# IsolatedPowerControl.net
KiCad netlist of a schematic drawn in EAGLE
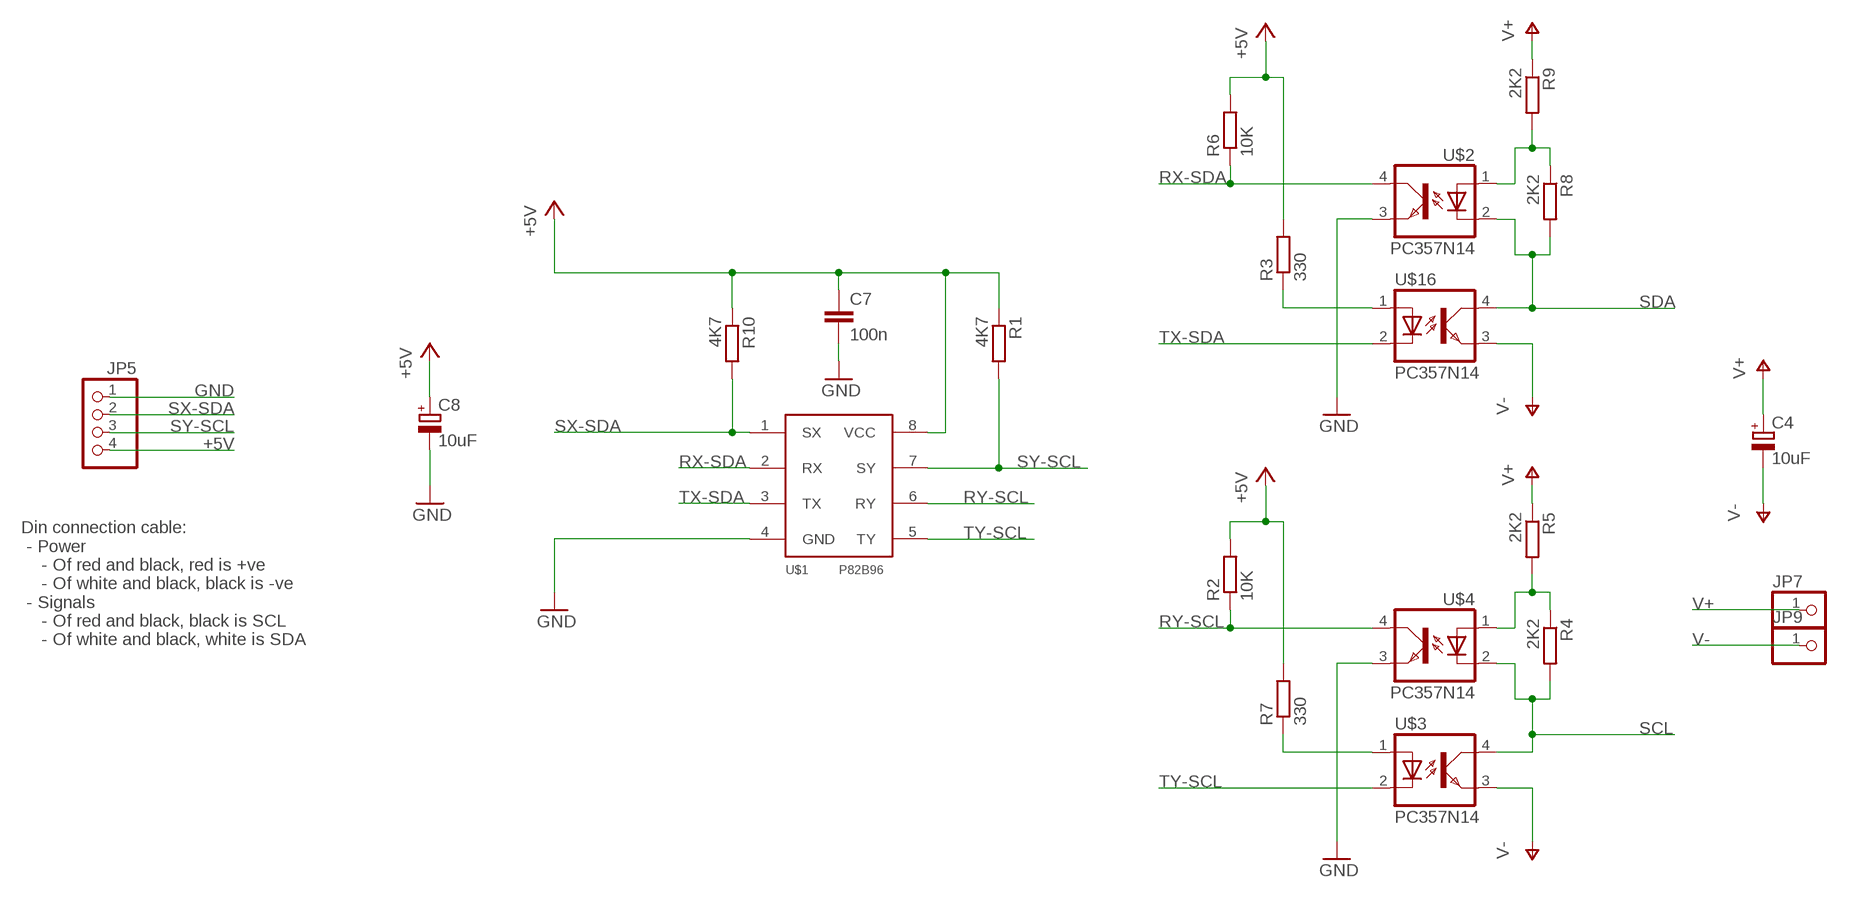
[diagram p0: schematic, sheet 1, part 1 of 2]
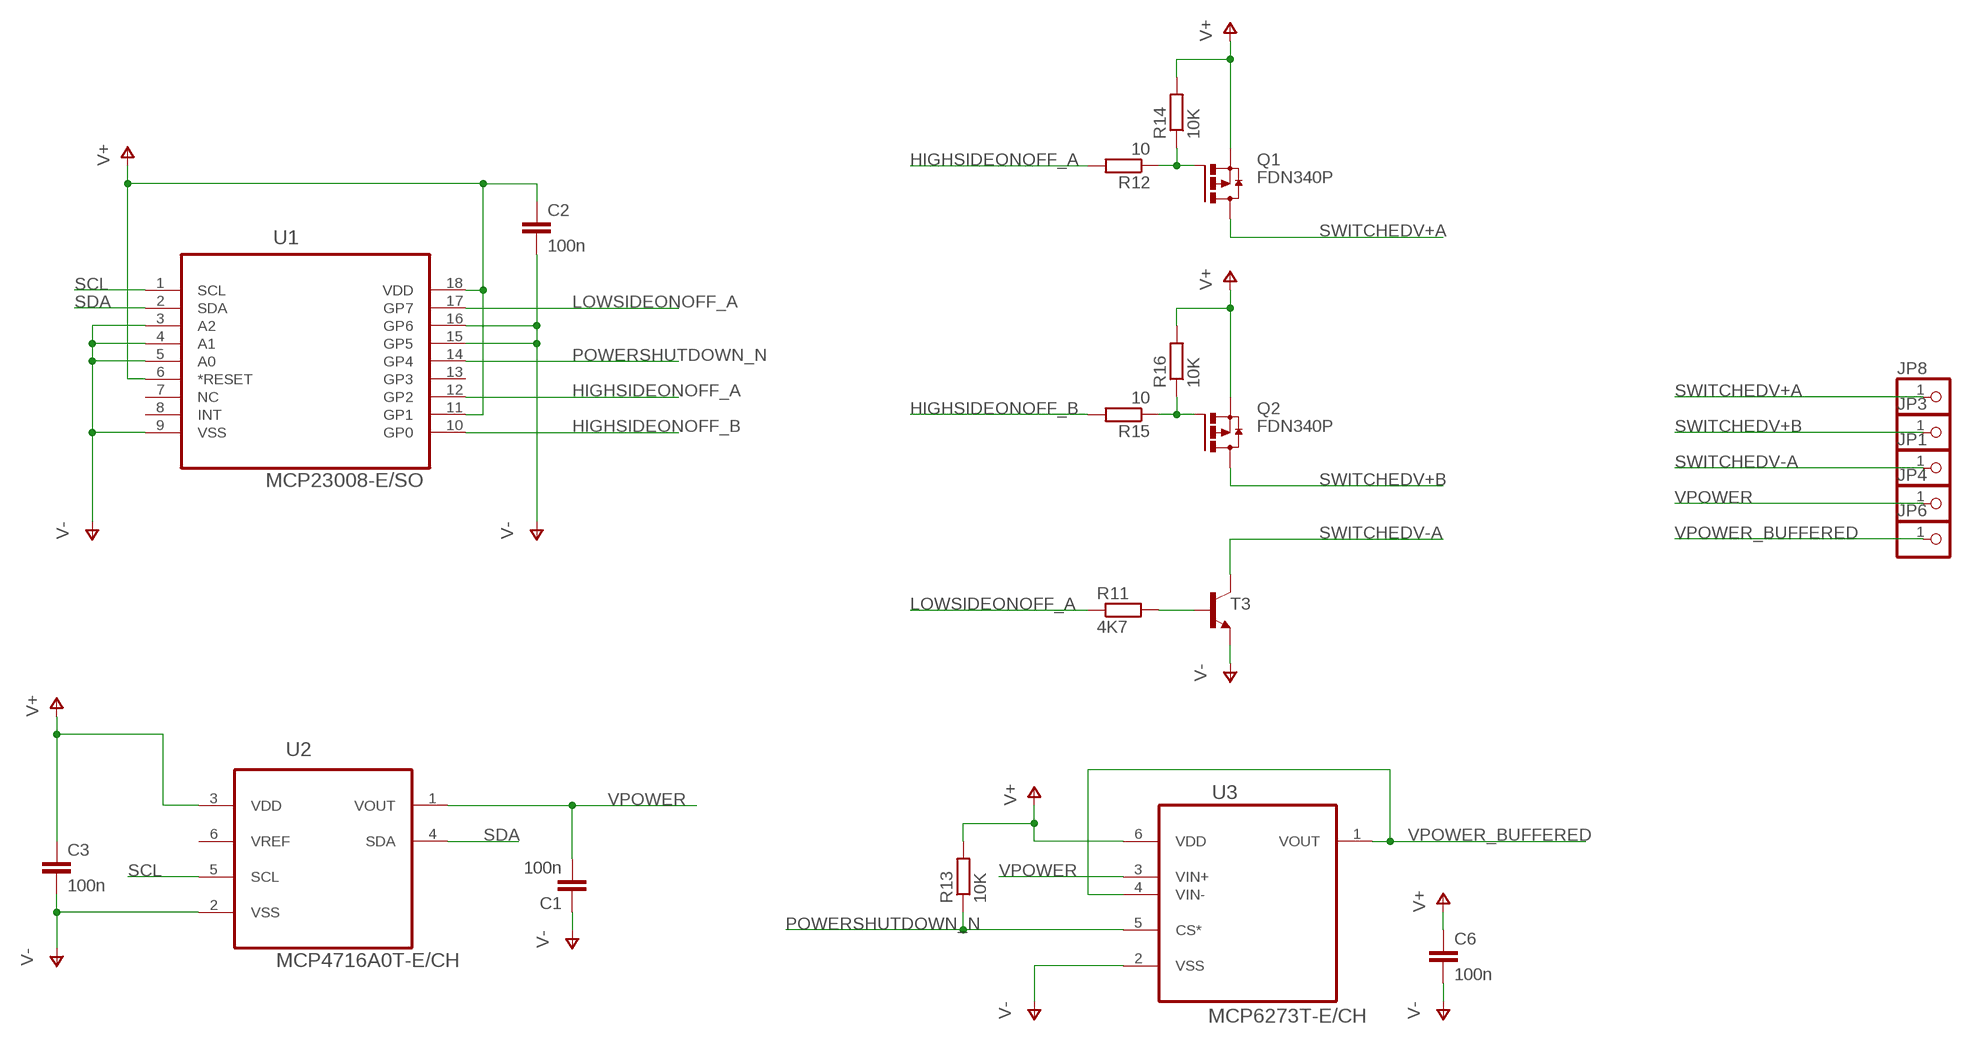
[diagram p1: schematic, sheet 1, part 2 of 2]

(export (version "E")
  (design (tool "Eeschema 10.0.6"))
  (components
    (comp (ref "C1")
      (value "100n")
      (footprint "eagle-import:C1206K")
      (libsource (lib "eagle-import") (part "C-EUC1206K"))
    )
    (comp (ref "C2")
      (value "100n")
      (footprint "eagle-import:C1206K")
      (libsource (lib "eagle-import") (part "C-EUC1206K"))
    )
    (comp (ref "C3")
      (value "100n")
      (footprint "eagle-import:C1206K")
      (libsource (lib "eagle-import") (part "C-EUC1206K"))
    )
    (comp (ref "C4")
      (value "10uF")
      (footprint "eagle-import:E2-5")
      (libsource (lib "eagle-import") (part "CPOL-EUE2-5"))
    )
    (comp (ref "C6")
      (value "100n")
      (footprint "eagle-import:C1206K")
      (libsource (lib "eagle-import") (part "C-EUC1206K"))
    )
    (comp (ref "C7")
      (value "100n")
      (footprint "eagle-import:C1206K")
      (libsource (lib "eagle-import") (part "C-EUC1206K"))
    )
    (comp (ref "C8")
      (value "10uF")
      (footprint "eagle-import:E2-5")
      (libsource (lib "eagle-import") (part "CPOL-EUE2-5"))
    )
    (comp (ref "JP1")
      (value "PINHD-1X1LARGEPAD")
      (footprint "eagle-import:1X01-LARGEPAD")
      (libsource (lib "eagle-import") (part "PINHD-1X1LARGEPAD"))
    )
    (comp (ref "JP3")
      (value "PINHD-1X1LARGEPAD")
      (footprint "eagle-import:1X01-LARGEPAD")
      (libsource (lib "eagle-import") (part "PINHD-1X1LARGEPAD"))
    )
    (comp (ref "JP4")
      (value "PINHD-1X1LARGEPAD")
      (footprint "eagle-import:1X01-LARGEPAD")
      (libsource (lib "eagle-import") (part "PINHD-1X1LARGEPAD"))
    )
    (comp (ref "JP5")
      (value "PINHD-1X4")
      (footprint "eagle-import:1X04")
      (libsource (lib "eagle-import") (part "PINHD-1X4"))
    )
    (comp (ref "JP6")
      (value "PINHD-1X1LARGEPAD")
      (footprint "eagle-import:1X01-LARGEPAD")
      (libsource (lib "eagle-import") (part "PINHD-1X1LARGEPAD"))
    )
    (comp (ref "JP7")
      (value "PINHD-1X1LARGEPAD")
      (footprint "eagle-import:1X01-LARGEPAD")
      (libsource (lib "eagle-import") (part "PINHD-1X1LARGEPAD"))
    )
    (comp (ref "JP8")
      (value "PINHD-1X1LARGEPAD")
      (footprint "eagle-import:1X01-LARGEPAD")
      (libsource (lib "eagle-import") (part "PINHD-1X1LARGEPAD"))
    )
    (comp (ref "JP9")
      (value "PINHD-1X1LARGEPAD")
      (footprint "eagle-import:1X01-LARGEPAD")
      (libsource (lib "eagle-import") (part "PINHD-1X1LARGEPAD"))
    )
    (comp (ref "Q1")
      (value "FDN340P")
      (footprint "eagle-import:SUPER-SOT3")
      (libsource (lib "eagle-import") (part "FDN360P"))
    )
    (comp (ref "Q2")
      (value "FDN340P")
      (footprint "eagle-import:SUPER-SOT3")
      (libsource (lib "eagle-import") (part "FDN360P"))
    )
    (comp (ref "R1")
      (value "4K7")
      (footprint "eagle-import:R0402")
      (libsource (lib "eagle-import") (part "R-EU_R0402"))
    )
    (comp (ref "R2")
      (value "10K")
      (footprint "eagle-import:R0805")
      (libsource (lib "eagle-import") (part "R-EU_R0805"))
    )
    (comp (ref "R3")
      (value "330")
      (footprint "eagle-import:R0402")
      (libsource (lib "eagle-import") (part "R-EU_R0402"))
    )
    (comp (ref "R4")
      (value "2K2")
      (footprint "eagle-import:R0402")
      (libsource (lib "eagle-import") (part "R-EU_R0402"))
    )
    (comp (ref "R5")
      (value "2K2")
      (footprint "eagle-import:R0402")
      (libsource (lib "eagle-import") (part "R-EU_R0402"))
    )
    (comp (ref "R6")
      (value "10K")
      (footprint "eagle-import:R0805")
      (libsource (lib "eagle-import") (part "R-EU_R0805"))
    )
    (comp (ref "R7")
      (value "330")
      (footprint "eagle-import:R0402")
      (libsource (lib "eagle-import") (part "R-EU_R0402"))
    )
    (comp (ref "R8")
      (value "2K2")
      (footprint "eagle-import:R0402")
      (libsource (lib "eagle-import") (part "R-EU_R0402"))
    )
    (comp (ref "R9")
      (value "2K2")
      (footprint "eagle-import:R0402")
      (libsource (lib "eagle-import") (part "R-EU_R0402"))
    )
    (comp (ref "R10")
      (value "4K7")
      (footprint "eagle-import:R0402")
      (libsource (lib "eagle-import") (part "R-EU_R0402"))
    )
    (comp (ref "R11")
      (value "4K7")
      (footprint "eagle-import:R0402")
      (libsource (lib "eagle-import") (part "R-EU_R0402"))
    )
    (comp (ref "R12")
      (value "10")
      (footprint "eagle-import:R0603")
      (libsource (lib "eagle-import") (part "R-EU_R0603"))
    )
    (comp (ref "R13")
      (value "10K")
      (footprint "eagle-import:R0805")
      (libsource (lib "eagle-import") (part "R-EU_R0805"))
    )
    (comp (ref "R14")
      (value "10K")
      (footprint "eagle-import:R0805")
      (libsource (lib "eagle-import") (part "R-EU_R0805"))
    )
    (comp (ref "R15")
      (value "10")
      (footprint "eagle-import:R0603")
      (libsource (lib "eagle-import") (part "R-EU_R0603"))
    )
    (comp (ref "R16")
      (value "10K")
      (footprint "eagle-import:R0805")
      (libsource (lib "eagle-import") (part "R-EU_R0805"))
    )
    (comp (ref "T3")
      (value "MMBTA42LT1-NPN-SOT23-BEC")
      (footprint "eagle-import:SOT23-BEC")
      (libsource (lib "eagle-import") (part "-NPN-SOT23-BECMMBTA42LT1"))
    )
    (comp (ref "U$1")
      (value "P82B96")
      (footprint "eagle-import:SOIC8")
      (libsource (lib "eagle-import") (part "P82B96"))
    )
    (comp (ref "U$2")
      (value "PC357N14")
      (footprint "eagle-import:MINI-FLAT-4-DS")
      (libsource (lib "eagle-import") (part "PC357N14"))
    )
    (comp (ref "U$3")
      (value "PC357N14")
      (footprint "eagle-import:MINI-FLAT-4-DS")
      (libsource (lib "eagle-import") (part "PC357N14"))
    )
    (comp (ref "U$4")
      (value "PC357N14")
      (footprint "eagle-import:MINI-FLAT-4-DS")
      (libsource (lib "eagle-import") (part "PC357N14"))
    )
    (comp (ref "U$16")
      (value "PC357N14")
      (footprint "eagle-import:MINI-FLAT-4-DS")
      (libsource (lib "eagle-import") (part "PC357N14"))
    )
    (comp (ref "U1")
      (value "MCP23008-E/SO")
      (footprint "eagle-import:SOIC127P1030X265-18N")
      (libsource (lib "eagle-import") (part "MCP23008-E/SO"))
    )
    (comp (ref "U2")
      (value "MCP4716A0T-E/CH")
      (footprint "eagle-import:SOT95P270X145-6N")
      (libsource (lib "eagle-import") (part "MCP4716A0T-E/CH"))
    )
    (comp (ref "U3")
      (value "MCP6273T-E/CH")
      (footprint "eagle-import:SOT95P280X145-6N")
      (libsource (lib "eagle-import") (part "MCP6273T-E/CH"))
    )
  )
  (nets
    (net (code "1") (name "+5V") (class "Default")
      (node (ref "C7") (pin "1") (pinfunction "1_1") (pintype "passive"))
      (node (ref "C8") (pin "+") (pinfunction "+_+") (pintype "passive"))
      (node (ref "JP5") (pin "4") (pinfunction "4_4") (pintype "passive"))
      (node (ref "R1") (pin "1") (pinfunction "1_1") (pintype "passive"))
      (node (ref "R10") (pin "1") (pinfunction "1_1") (pintype "passive"))
      (node (ref "R2") (pin "2") (pinfunction "2_2") (pintype "passive"))
      (node (ref "R3") (pin "2") (pinfunction "2_2") (pintype "passive"))
      (node (ref "R6") (pin "2") (pinfunction "2_2") (pintype "passive"))
      (node (ref "R7") (pin "2") (pinfunction "2_2") (pintype "passive"))
      (node (ref "U$1") (pin "8") (pinfunction "VCC_8") (pintype "bidirectional"))
    )
    (net (code "2") (name "/HIGHSIDEONOFF_A") (class "Default")
      (node (ref "R12") (pin "2") (pinfunction "2_2") (pintype "passive"))
      (node (ref "U1") (pin "12") (pinfunction "GP2_12") (pintype "passive"))
    )
    (net (code "3") (name "/HIGHSIDEONOFF_B") (class "Default")
      (node (ref "R15") (pin "2") (pinfunction "2_2") (pintype "passive"))
      (node (ref "U1") (pin "10") (pinfunction "GP0_10") (pintype "passive"))
    )
    (net (code "4") (name "/LOWSIDEONOFF_A") (class "Default")
      (node (ref "R11") (pin "1") (pinfunction "1_1") (pintype "passive"))
      (node (ref "U1") (pin "17") (pinfunction "GP7_17") (pintype "passive"))
    )
    (net (code "5") (name "/POWERSHUTDOWN_N") (class "Default")
      (node (ref "R13") (pin "1") (pinfunction "1_1") (pintype "passive"))
      (node (ref "U1") (pin "14") (pinfunction "GP4_14") (pintype "passive"))
      (node (ref "U3") (pin "5") (pinfunction "CS*_5") (pintype "passive"))
    )
    (net (code "6") (name "/RX-SDA") (class "Default")
      (node (ref "R6") (pin "1") (pinfunction "1_1") (pintype "passive"))
      (node (ref "U$1") (pin "2") (pinfunction "RX_2") (pintype "bidirectional"))
      (node (ref "U$2") (pin "4") (pinfunction "COL_4") (pintype "passive"))
    )
    (net (code "7") (name "/RY-SCL") (class "Default")
      (node (ref "R2") (pin "1") (pinfunction "1_1") (pintype "passive"))
      (node (ref "U$1") (pin "6") (pinfunction "RY_6") (pintype "bidirectional"))
      (node (ref "U$4") (pin "4") (pinfunction "COL_4") (pintype "passive"))
    )
    (net (code "8") (name "/SCL") (class "Default")
      (node (ref "R4") (pin "2") (pinfunction "2_2") (pintype "passive"))
      (node (ref "U$3") (pin "4") (pinfunction "COL_4") (pintype "passive"))
      (node (ref "U$4") (pin "2") (pinfunction "C_2") (pintype "passive"))
      (node (ref "U1") (pin "1") (pinfunction "SCL_1") (pintype "input"))
      (node (ref "U2") (pin "5") (pinfunction "SCL_5") (pintype "input"))
    )
    (net (code "9") (name "/SDA") (class "Default")
      (node (ref "R8") (pin "2") (pinfunction "2_2") (pintype "passive"))
      (node (ref "U$16") (pin "4") (pinfunction "COL_4") (pintype "passive"))
      (node (ref "U$2") (pin "2") (pinfunction "C_2") (pintype "passive"))
      (node (ref "U1") (pin "2") (pinfunction "SDA_2") (pintype "passive"))
      (node (ref "U2") (pin "4") (pinfunction "SDA_4") (pintype "bidirectional"))
    )
    (net (code "10") (name "/SWITCHEDV+A") (class "Default")
      (node (ref "JP8") (pin "1") (pinfunction "1_1") (pintype "passive"))
      (node (ref "Q1") (pin "3") (pinfunction "D_3") (pintype "passive"))
    )
    (net (code "11") (name "/SWITCHEDV+B") (class "Default")
      (node (ref "JP3") (pin "1") (pinfunction "1_1") (pintype "passive"))
      (node (ref "Q2") (pin "3") (pinfunction "D_3") (pintype "passive"))
    )
    (net (code "12") (name "/SWITCHEDV-A") (class "Default")
      (node (ref "JP1") (pin "1") (pinfunction "1_1") (pintype "passive"))
      (node (ref "T3") (pin "C") (pinfunction "C_C") (pintype "passive"))
    )
    (net (code "13") (name "/SX-SDA") (class "Default")
      (node (ref "JP5") (pin "2") (pinfunction "2_2") (pintype "passive"))
      (node (ref "R10") (pin "2") (pinfunction "2_2") (pintype "passive"))
      (node (ref "U$1") (pin "1") (pinfunction "SX_1") (pintype "bidirectional"))
    )
    (net (code "14") (name "/SY-SCL") (class "Default")
      (node (ref "JP5") (pin "3") (pinfunction "3_3") (pintype "passive"))
      (node (ref "R1") (pin "2") (pinfunction "2_2") (pintype "passive"))
      (node (ref "U$1") (pin "7") (pinfunction "SY_7") (pintype "bidirectional"))
    )
    (net (code "15") (name "/TX-SDA") (class "Default")
      (node (ref "U$1") (pin "3") (pinfunction "TX_3") (pintype "bidirectional"))
      (node (ref "U$16") (pin "2") (pinfunction "C_2") (pintype "passive"))
    )
    (net (code "16") (name "/TY-SCL") (class "Default")
      (node (ref "U$1") (pin "5") (pinfunction "TY_5") (pintype "bidirectional"))
      (node (ref "U$3") (pin "2") (pinfunction "C_2") (pintype "passive"))
    )
    (net (code "17") (name "/VPOWER") (class "Default")
      (node (ref "C1") (pin "2") (pinfunction "2_2") (pintype "passive"))
      (node (ref "JP4") (pin "1") (pinfunction "1_1") (pintype "passive"))
      (node (ref "U2") (pin "1") (pinfunction "VOUT_1") (pintype "output"))
      (node (ref "U3") (pin "3") (pinfunction "VIN+_3") (pintype "input"))
    )
    (net (code "18") (name "/VPOWER_BUFFERED") (class "Default")
      (node (ref "JP6") (pin "1") (pinfunction "1_1") (pintype "passive"))
      (node (ref "U3") (pin "1") (pinfunction "VOUT_1") (pintype "output"))
      (node (ref "U3") (pin "4") (pinfunction "VIN-_4") (pintype "input"))
    )
    (net (code "19") (name "GND") (class "Default")
      (node (ref "C7") (pin "2") (pinfunction "2_2") (pintype "passive"))
      (node (ref "C8") (pin "-") (pinfunction "-_-") (pintype "passive"))
      (node (ref "JP5") (pin "1") (pinfunction "1_1") (pintype "passive"))
      (node (ref "U$1") (pin "4") (pinfunction "GND_4") (pintype "bidirectional"))
      (node (ref "U$2") (pin "3") (pinfunction "EMIT_3") (pintype "passive"))
      (node (ref "U$4") (pin "3") (pinfunction "EMIT_3") (pintype "passive"))
    )
    (net (code "20") (name "Net-(Q1-G)") (class "Default")
      (node (ref "Q1") (pin "1") (pinfunction "G_1") (pintype "passive"))
      (node (ref "R12") (pin "1") (pinfunction "1_1") (pintype "passive"))
      (node (ref "R14") (pin "1") (pinfunction "1_1") (pintype "passive"))
    )
    (net (code "21") (name "Net-(Q2-G)") (class "Default")
      (node (ref "Q2") (pin "1") (pinfunction "G_1") (pintype "passive"))
      (node (ref "R15") (pin "1") (pinfunction "1_1") (pintype "passive"))
      (node (ref "R16") (pin "1") (pinfunction "1_1") (pintype "passive"))
    )
    (net (code "22") (name "Net-(R11-Pad2)") (class "Default")
      (node (ref "R11") (pin "2") (pinfunction "2_2") (pintype "passive"))
      (node (ref "T3") (pin "B") (pinfunction "B_B") (pintype "passive"))
    )
    (net (code "23") (name "Net-(U$2-A)") (class "Default")
      (node (ref "R8") (pin "1") (pinfunction "1_1") (pintype "passive"))
      (node (ref "R9") (pin "2") (pinfunction "2_2") (pintype "passive"))
      (node (ref "U$2") (pin "1") (pinfunction "A_1") (pintype "passive"))
    )
    (net (code "24") (name "Net-(U$3-A)") (class "Default")
      (node (ref "R7") (pin "1") (pinfunction "1_1") (pintype "passive"))
      (node (ref "U$3") (pin "1") (pinfunction "A_1") (pintype "passive"))
    )
    (net (code "25") (name "Net-(U$4-A)") (class "Default")
      (node (ref "R4") (pin "1") (pinfunction "1_1") (pintype "passive"))
      (node (ref "R5") (pin "2") (pinfunction "2_2") (pintype "passive"))
      (node (ref "U$4") (pin "1") (pinfunction "A_1") (pintype "passive"))
    )
    (net (code "26") (name "Net-(U$16-A)") (class "Default")
      (node (ref "R3") (pin "1") (pinfunction "1_1") (pintype "passive"))
      (node (ref "U$16") (pin "1") (pinfunction "A_1") (pintype "passive"))
    )
    (net (code "27") (name "V+") (class "Default")
      (node (ref "C2") (pin "1") (pinfunction "1_1") (pintype "passive"))
      (node (ref "C3") (pin "1") (pinfunction "1_1") (pintype "passive"))
      (node (ref "C4") (pin "+") (pinfunction "+_+") (pintype "passive"))
      (node (ref "C6") (pin "1") (pinfunction "1_1") (pintype "passive"))
      (node (ref "JP7") (pin "1") (pinfunction "1_1") (pintype "passive"))
      (node (ref "Q1") (pin "2") (pinfunction "S_2") (pintype "passive"))
      (node (ref "Q2") (pin "2") (pinfunction "S_2") (pintype "passive"))
      (node (ref "R13") (pin "2") (pinfunction "2_2") (pintype "passive"))
      (node (ref "R14") (pin "2") (pinfunction "2_2") (pintype "passive"))
      (node (ref "R16") (pin "2") (pinfunction "2_2") (pintype "passive"))
      (node (ref "R5") (pin "1") (pinfunction "1_1") (pintype "passive"))
      (node (ref "R9") (pin "1") (pinfunction "1_1") (pintype "passive"))
      (node (ref "U1") (pin "11") (pinfunction "GP1_11") (pintype "passive"))
      (node (ref "U1") (pin "18") (pinfunction "VDD_18") (pintype "power_in"))
      (node (ref "U1") (pin "6") (pinfunction "*RESET_6") (pintype "input"))
      (node (ref "U2") (pin "3") (pinfunction "VDD_3") (pintype "power_in"))
      (node (ref "U3") (pin "6") (pinfunction "VDD_6") (pintype "power_in"))
    )
    (net (code "28") (name "V-") (class "Default")
      (node (ref "C1") (pin "1") (pinfunction "1_1") (pintype "passive"))
      (node (ref "C2") (pin "2") (pinfunction "2_2") (pintype "passive"))
      (node (ref "C3") (pin "2") (pinfunction "2_2") (pintype "passive"))
      (node (ref "C4") (pin "-") (pinfunction "-_-") (pintype "passive"))
      (node (ref "C6") (pin "2") (pinfunction "2_2") (pintype "passive"))
      (node (ref "JP9") (pin "1") (pinfunction "1_1") (pintype "passive"))
      (node (ref "T3") (pin "E") (pinfunction "E_E") (pintype "passive"))
      (node (ref "U$16") (pin "3") (pinfunction "EMIT_3") (pintype "passive"))
      (node (ref "U$3") (pin "3") (pinfunction "EMIT_3") (pintype "passive"))
      (node (ref "U1") (pin "15") (pinfunction "GP5_15") (pintype "passive"))
      (node (ref "U1") (pin "16") (pinfunction "GP6_16") (pintype "passive"))
      (node (ref "U1") (pin "3") (pinfunction "A2_3") (pintype "passive"))
      (node (ref "U1") (pin "4") (pinfunction "A1_4") (pintype "input"))
      (node (ref "U1") (pin "5") (pinfunction "A0_5") (pintype "input"))
      (node (ref "U1") (pin "9") (pinfunction "VSS_9") (pintype "passive"))
      (node (ref "U2") (pin "2") (pinfunction "VSS_2") (pintype "passive"))
      (node (ref "U3") (pin "2") (pinfunction "VSS_2") (pintype "power_in"))
    )
    (net (code "29") (name "unconnected-(U1-GP3-Pad13)") (class "Default")
      (node (ref "U1") (pin "13") (pinfunction "GP3_13") (pintype "passive"))
    )
    (net (code "30") (name "unconnected-(U1-INT-Pad8)") (class "Default")
      (node (ref "U1") (pin "8") (pinfunction "INT_8") (pintype "output"))
    )
    (net (code "31") (name "unconnected-(U1-NC-Pad7)") (class "Default")
      (node (ref "U1") (pin "7") (pinfunction "NC_7") (pintype "input"))
    )
    (net (code "32") (name "unconnected-(U2-VREF-Pad6)") (class "Default")
      (node (ref "U2") (pin "6") (pinfunction "VREF_6") (pintype "input"))
    )
  )
)
